# 1_PowerSupply.net
KiCad netlist of a schematic drawn in Altium Designer
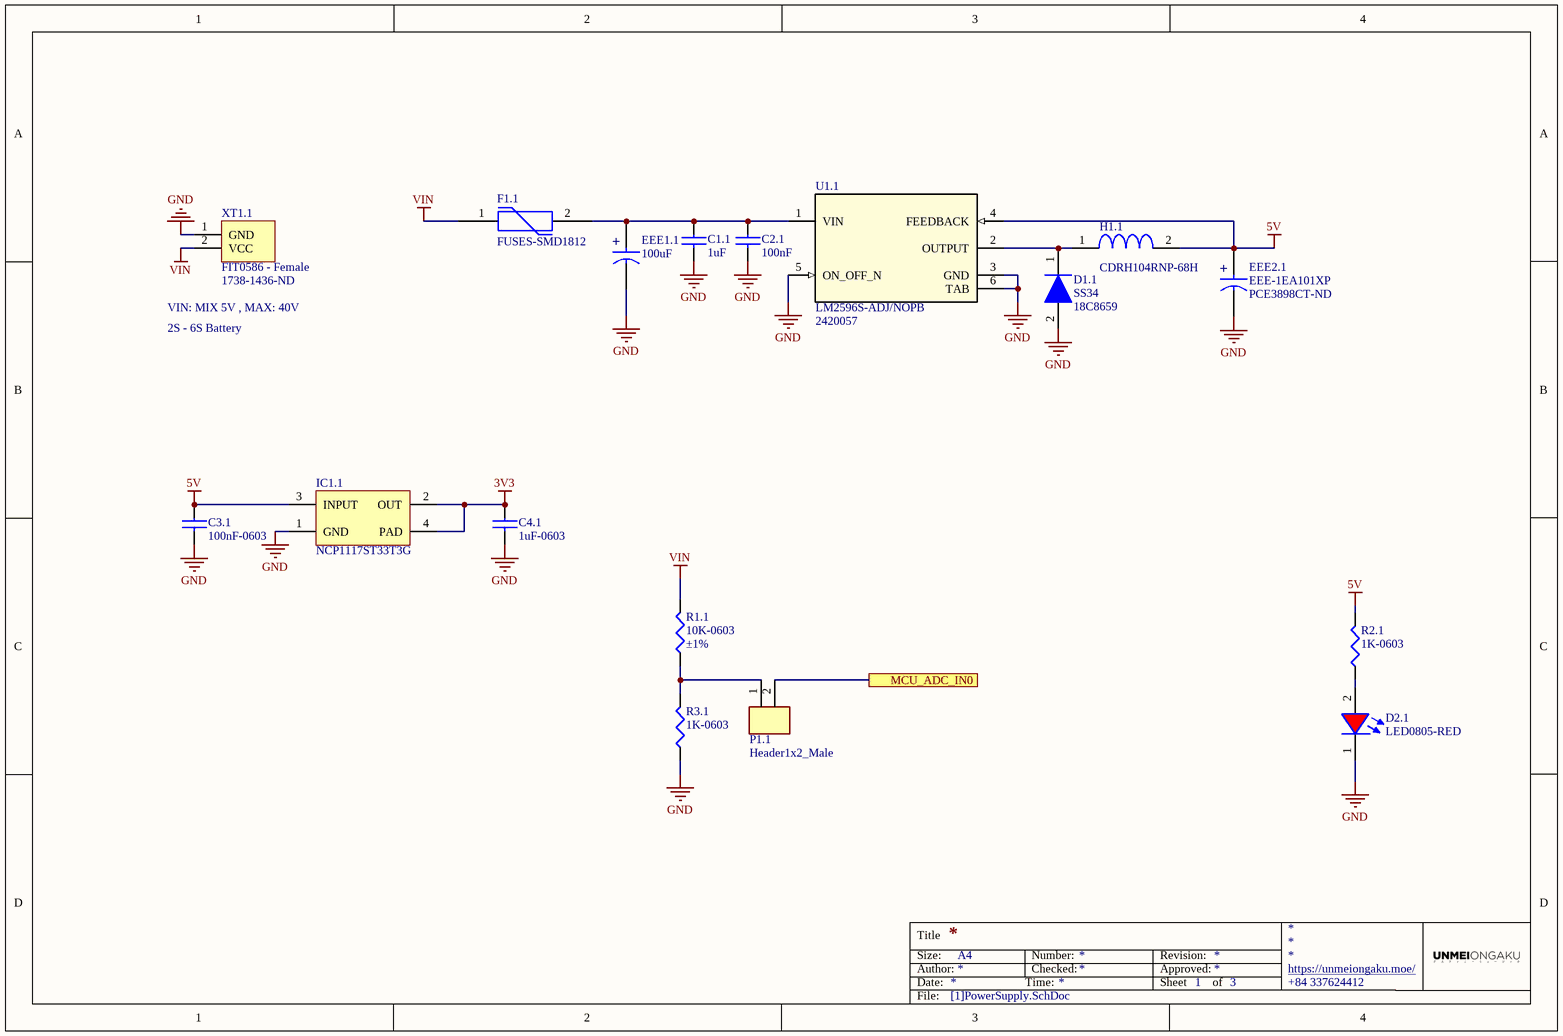
[diagram p0: [1]PowerSupply.SchDoc]

(export (version "E")
  (design (tool "Eeschema 10.0.6"))
  (components
    (comp (ref "C1.1")
      (value "1uF")
      (footprint "CAP0603")
      (description "CAP CER 1UF 16V X7R 0603")
      (fields (field (name "TOLERANCE") "±10%"))
      (libsource (lib "Minh_Lib") (part "CC0603KRX7R7BB105"))
    )
    (comp (ref "C2.1")
      (value "100nF")
      (footprint "CAP0603")
      (description "CAP CER 0.1UF 50V X7R 0603")
      (fields (field (name "TOLERANCE") "±10%"))
      (libsource (lib "Minh_Lib") (part "CC0603KRX7R9BB104"))
    )
    (comp (ref "C3.1")
      (value "100nF-0603")
      (footprint "CAP0603")
      (description "CAP CER 0.1UF 50V X7R 0603")
      (fields (field (name "TOLERANCE") "±10%"))
      (libsource (lib "Minh_Lib") (part "CC0603KRX7R9BB104"))
    )
    (comp (ref "C4.1")
      (value "1uF-0603")
      (footprint "CAP0603")
      (description "CAP CER 1UF 16V X7R 0603")
      (fields (field (name "TOLERANCE") "±10%"))
      (libsource (lib "Minh_Lib") (part "CC0603KRX7R7BB105"))
    )
    (comp (ref "D1.1")
      (value "SS34")
      (footprint "SS34 - 1N5822 / DO-214AA, SMA")
      (description "SS Series 500 mV 3 A 40 V Max Reverse Voltage Schottky Rectifier - DO-214AB")
      (fields
        (field (name "MANUFACTURER") "ON Semiconductor / Fairchild")
        (field (name "VOLTAGE") "40V")
        (field (name "SUPPLIER PART NUMBER 1") "18C8659")
      )
      (libsource (lib "Minh_Lib") (part "SS34"))
    )
    (comp (ref "D2.1")
      (value "LED0805-RED")
      (footprint "LED0805-RED")
      (libsource (lib "Minh_Lib") (part "LED0805-RED"))
    )
    (comp (ref "EEE1.1")
      (value "100uF")
      (footprint "CAPACITOR/ALU - SIZE D/SMD - 6.3X5.4")
      (description "Cap Aluminum 100uF 10V 20% (6.3 X 5.4mm) SMD 70mA 2000 hr 85°C T/R")
      (fields
        (field (name "MANUFACTURER") "Panasonic")
        (field (name "MANUFACTURER PART NUMBER") "EEE-1AA101SP")
      )
      (libsource (lib "Minh_Lib") (part "EEE-1AA101SP"))
    )
    (comp (ref "EEE2.1")
      (value "EEE-1EA101XP")
      (footprint "CAPACITOR/ALU - SIZE D8/SMD - 6.3X7.7")
      (description "Cap Aluminum 100uF 25V 20% (6.3 X 7.7mm) SMD 143mA 2000h 85°C T/R")
      (fields
        (field (name "MANUFACTURER") "Panasonic")
        (field (name "TOLERANCE") "20%")
        (field (name "SUPPLIER PART NUMBER 1") "PCE3898CT-ND")
      )
      (libsource (lib "Minh_Lib") (part "EEE-1EA101XP"))
    )
    (comp (ref "F1.1")
      (value "FUSES-SMD1812")
      (footprint "FUSES - SMD1812")
      (libsource (lib "Minh_Lib") (part "FUSES-SMD1812"))
    )
    (comp (ref "H1.1")
      (value "CDRH104RNP-68H")
      (footprint "CDRH104RNP")
      (description "Ind Power Shielded Wirewound 68uH 30% 100KHz Ferrite 1.42A Carrier T/R")
      (fields
        (field (name "MANUFACTURER") "Sumida")
        (field (name "MANUFACTURER PART NUMBER") "CDRH104RNP-680NC")
      )
      (libsource (lib "Minh_Lib") (part "CDRH104RNP-680NC"))
    )
    (comp (ref "IC1.1")
      (value "NCP1117ST33T3G")
      (footprint "SOT223-4M_AMS1117_3V3")
      (description "LDO Voltage Regulators 3.3V 1A Positive")
      (fields (field (name "MANUFACTURER") "ON Semiconductor"))
      (libsource (lib "Minh_Lib") (part "AMS1117 - 3V3"))
    )
    (comp (ref "P1.1")
      (value "Header1x2_Male")
      (footprint "Minh_Lib:HDR1x2_2.54_MALE")
      (description "Header1x2_2.54_MALE")
      (libsource (lib "Minh_Lib") (part "HDR1x2_2.54_MALE"))
    )
    (comp (ref "R1.1")
      (value "10K-0603")
      (footprint "RES0603 - 3D")
      (description "RES SMD 10K OHM 1% 1/10W 0603")
      (fields
        (field (name "MANUFACTURER") "Yageo")
        (field (name "MANUFACTURER PART NUMBER") "RC0603FR-0710KL")
        (field (name "TOLERANCE") "±1%")
      )
      (libsource (lib "Minh_Lib") (part "RC0603FR-0710KL"))
    )
    (comp (ref "R2.1")
      (value "1K-0603")
      (footprint "RES0603 - 3D")
      (description "RES SMD 1K OHM 5% 1/10W 0603")
      (fields (field (name "TOLERANCE") "±5%"))
      (libsource (lib "Minh_Lib") (part "RC0603JR-071KL"))
    )
    (comp (ref "R3.1")
      (value "1K-0603")
      (footprint "RES0603 - 3D")
      (description "RES SMD 1K OHM 5% 1/10W 0603")
      (fields (field (name "TOLERANCE") "±5%"))
      (libsource (lib "Minh_Lib") (part "RC0603JR-071KL"))
    )
    (comp (ref "U1.1")
      (value "LM2596S-ADJ/NOPB")
      (footprint "Minh_Lib:TO265-5")
      (description "Optoisolator 5KV Trans 4SMD / Optocoupler Dc-in 1-CH Transistor Dc-out 4-PIN PDIP SMD")
      (fields
        (field (name "PARTNUMBER") "LM2596SX-ADJ/NOPB")
        (field (name "MANUFACTURER") "Texas Instruments")
        (field (name "SUPPLIER PART NUMBER 1") "2420057")
        (field (name "COPYRIGHT") "Copyright (C) 2021 Ultra Librarian. All rights reserved.")
      )
      (libsource (lib "Minh_Lib") (part "LM2596S-ADJ/NOPB"))
    )
    (comp (ref "XT1.1")
      (value "FIT0586 - Female")
      (footprint "XT30U-M")
      (description "High Quality Gold Plated Male and Female Bullet Connector")
      (fields
        (field (name "MANUFACTURER") "DFRobot")
        (field (name "MANUFACTURER PART NUMBER") "FIT0586")
        (field (name "SUPPLIER PART NUMBER 1") "1738-1436-ND")
      )
      (libsource (lib "Minh_Lib") (part "FIT0586 - Female"))
    )
  )
  (nets
    (net (code "1") (name "/MCU_ADC_IN0") (class "Default")
      (node (ref "P1.1") (pin "2") (pinfunction "2_2") (pintype "passive"))
    )
    (net (code "2") (name "3V3") (class "Default")
      (node (ref "C4.1") (pin "1") (pinfunction "1_1") (pintype "passive"))
      (node (ref "IC1.1") (pin "2") (pinfunction "OUT_2") (pintype "passive"))
      (node (ref "IC1.1") (pin "4") (pinfunction "PAD_4") (pintype "passive"))
    )
    (net (code "3") (name "5V") (class "Default")
      (node (ref "C3.1") (pin "1") (pinfunction "1_1") (pintype "passive"))
      (node (ref "EEE2.1") (pin "1") (pinfunction "1_1") (pintype "passive"))
      (node (ref "H1.1") (pin "2") (pinfunction "2_2") (pintype "passive"))
      (node (ref "IC1.1") (pin "3") (pinfunction "INPUT_3") (pintype "power_in"))
      (node (ref "R2.1") (pin "2") (pinfunction "2_2") (pintype "passive"))
      (node (ref "U1.1") (pin "4") (pinfunction "FEEDBACK_4") (pintype "input"))
    )
    (net (code "4") (name "GND") (class "Default")
      (node (ref "C1.1") (pin "2") (pinfunction "2_2") (pintype "passive"))
      (node (ref "C2.1") (pin "2") (pinfunction "2_2") (pintype "passive"))
      (node (ref "C3.1") (pin "2") (pinfunction "2_2") (pintype "passive"))
      (node (ref "C4.1") (pin "2") (pinfunction "2_2") (pintype "passive"))
      (node (ref "D1.1") (pin "2") (pintype "passive"))
      (node (ref "D2.1") (pin "1") (pinfunction "+_1") (pintype "passive"))
      (node (ref "EEE1.1") (pin "2") (pinfunction "2_2") (pintype "passive"))
      (node (ref "EEE2.1") (pin "2") (pinfunction "2_2") (pintype "passive"))
      (node (ref "IC1.1") (pin "1") (pinfunction "GND_1") (pintype "power_in"))
      (node (ref "R3.1") (pin "1") (pinfunction "1_1") (pintype "passive"))
      (node (ref "U1.1") (pin "3") (pinfunction "GND_3") (pintype "power_in"))
      (node (ref "U1.1") (pin "5") (pinfunction "ON_OFF_N_5") (pintype "input"))
      (node (ref "U1.1") (pin "6") (pinfunction "TAB_6") (pintype "power_in"))
      (node (ref "XT1.1") (pin "1") (pinfunction "GND_1") (pintype "passive"))
    )
    (net (code "5") (name "Net-(D2.1-+-Pad2)") (class "Default")
      (node (ref "D2.1") (pin "2") (pinfunction "+_2") (pintype "passive"))
      (node (ref "R2.1") (pin "1") (pinfunction "1_1") (pintype "passive"))
    )
    (net (code "6") (name "Net-(F1.1-1)") (class "Default")
      (node (ref "C1.1") (pin "1") (pinfunction "1_1") (pintype "passive"))
      (node (ref "C2.1") (pin "1") (pinfunction "1_1") (pintype "passive"))
      (node (ref "EEE1.1") (pin "1") (pinfunction "1_1") (pintype "passive"))
      (node (ref "F1.1") (pin "2") (pinfunction "1_2") (pintype "passive"))
      (node (ref "U1.1") (pin "1") (pinfunction "VIN_1") (pintype "power_in"))
    )
    (net (code "7") (name "Net-(P1.1-Pad1)") (class "Default")
      (node (ref "P1.1") (pin "1") (pinfunction "1_1") (pintype "passive"))
      (node (ref "R1.1") (pin "1") (pinfunction "1_1") (pintype "passive"))
      (node (ref "R3.1") (pin "2") (pinfunction "2_2") (pintype "passive"))
    )
    (net (code "8") (name "Net-(U1.1-OUTPUT)") (class "Default")
      (node (ref "D1.1") (pin "1") (pintype "passive"))
      (node (ref "H1.1") (pin "1") (pinfunction "1_1") (pintype "passive"))
      (node (ref "U1.1") (pin "2") (pinfunction "OUTPUT_2") (pintype "power_in"))
    )
    (net (code "9") (name "VIN") (class "Default")
      (node (ref "F1.1") (pin "1") (pinfunction "0_1") (pintype "passive"))
      (node (ref "R1.1") (pin "2") (pinfunction "2_2") (pintype "passive"))
      (node (ref "XT1.1") (pin "2") (pinfunction "VCC_2") (pintype "passive"))
    )
  )
)
